# design.net
KiCad netlist of a schematic drawn in EAGLE
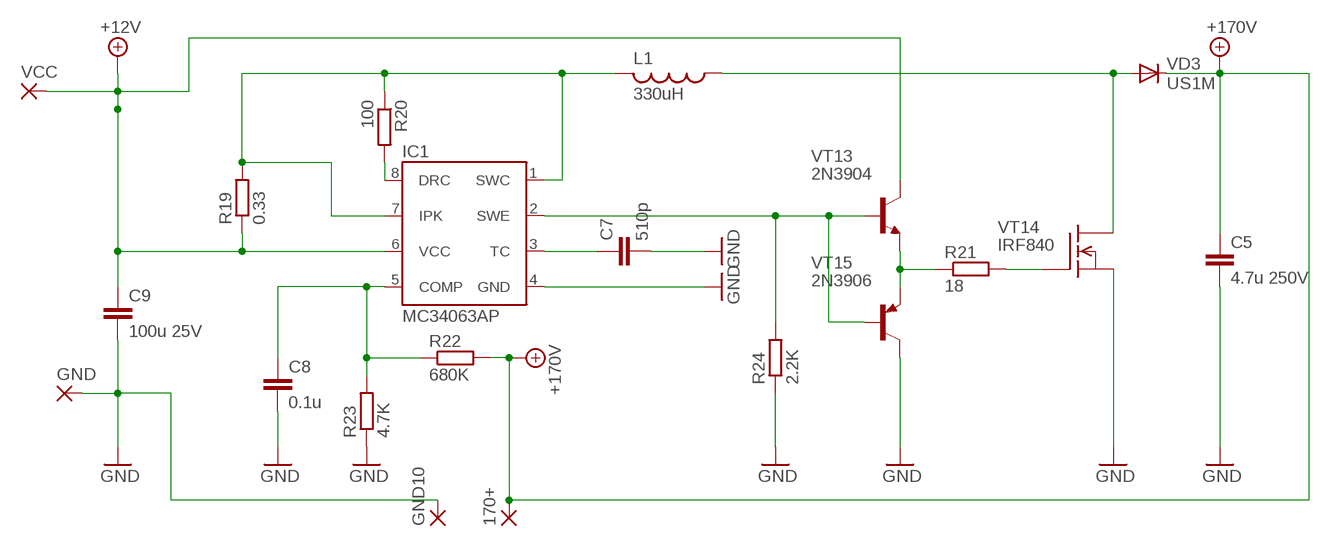
[diagram p0: schematic, sheet 1]

(export (version "E")
  (design (tool "Eeschema 10.0.6"))
  (components
    (comp (ref "170+")
      (value "2,54/0,8")
      (footprint "eagle-import:2,54_0,8")
      (libsource (lib "eagle-import") (part "2,54/0,8"))
    )
    (comp (ref "C5")
      (value "4.7u 250V")
      (footprint "eagle-import:C025-030X050")
      (libsource (lib "eagle-import") (part "C-EU025-030X050"))
    )
    (comp (ref "C7")
      (value "510p")
      (footprint "eagle-import:C025-030X050")
      (libsource (lib "eagle-import") (part "C-EU025-030X050"))
    )
    (comp (ref "C8")
      (value "0.1u")
      (footprint "eagle-import:C025-030X050")
      (libsource (lib "eagle-import") (part "C-EU025-030X050"))
    )
    (comp (ref "C9")
      (value "100u 25V")
      (footprint "eagle-import:C025-030X050")
      (libsource (lib "eagle-import") (part "C-EU025-030X050"))
    )
    (comp (ref "GND")
      (value "2,54/0,8")
      (footprint "eagle-import:2,54_0,8")
      (libsource (lib "eagle-import") (part "2,54/0,8"))
    )
    (comp (ref "GND10")
      (value "2,54/0,8")
      (footprint "eagle-import:2,54_0,8")
      (libsource (lib "eagle-import") (part "2,54/0,8"))
    )
    (comp (ref "IC1")
      (value "MC34063AP")
      (footprint "eagle-import:DIL-08")
      (libsource (lib "eagle-import") (part "MC34063AP"))
    )
    (comp (ref "L1")
      (value "330uH")
      (footprint "eagle-import:0204_5")
      (libsource (lib "eagle-import") (part "L-US0204/5"))
    )
    (comp (ref "R19")
      (value "0.33")
      (footprint "eagle-import:0204_5")
      (libsource (lib "eagle-import") (part "R-EU_0204/5"))
    )
    (comp (ref "R20")
      (value "100")
      (footprint "eagle-import:0204_5")
      (libsource (lib "eagle-import") (part "R-EU_0204/5"))
    )
    (comp (ref "R21")
      (value "18")
      (footprint "eagle-import:0204_5")
      (libsource (lib "eagle-import") (part "R-EU_0204/5"))
    )
    (comp (ref "R22")
      (value "680K")
      (footprint "eagle-import:0204_5")
      (libsource (lib "eagle-import") (part "R-EU_0204/5"))
    )
    (comp (ref "R23")
      (value "4.7K")
      (footprint "eagle-import:0204_5")
      (libsource (lib "eagle-import") (part "R-EU_0204/5"))
    )
    (comp (ref "R24")
      (value "2.2K")
      (footprint "eagle-import:0204_5")
      (libsource (lib "eagle-import") (part "R-EU_0204/5"))
    )
    (comp (ref "VCC")
      (value "2,54/0,8")
      (footprint "eagle-import:2,54_0,8")
      (libsource (lib "eagle-import") (part "2,54/0,8"))
    )
    (comp (ref "VD3")
      (value "US1M")
      (footprint "eagle-import:DO41-10")
      (libsource (lib "eagle-import") (part "1N4004"))
    )
    (comp (ref "VT13")
      (value "2N3904")
      (footprint "eagle-import:TO92")
      (libsource (lib "eagle-import") (part "2N3904"))
    )
    (comp (ref "VT14")
      (value "IRF840")
      (footprint "eagle-import:TO220")
      (libsource (lib "eagle-import") (part "IRF840"))
    )
    (comp (ref "VT15")
      (value "2N3906")
      (footprint "eagle-import:TO92")
      (libsource (lib "eagle-import") (part "2N3906"))
    )
  )
  (nets
    (net (code "1") (name "+12V") (class "Default")
      (node (ref "C9") (pin "1") (pinfunction "1_1") (pintype "passive"))
      (node (ref "IC1") (pin "6") (pinfunction "VCC_6") (pintype "power_in"))
      (node (ref "R19") (pin "1") (pinfunction "1_1") (pintype "passive"))
      (node (ref "VCC") (pin "1") (pinfunction "P_1") (pintype "passive"))
      (node (ref "VT13") (pin "1") (pinfunction "C_1") (pintype "passive"))
    )
    (net (code "2") (name "+170V") (class "Default")
      (node (ref "170+") (pin "1") (pinfunction "P_1") (pintype "passive"))
      (node (ref "C5") (pin "1") (pinfunction "1_1") (pintype "passive"))
      (node (ref "R22") (pin "2") (pinfunction "2_2") (pintype "passive"))
      (node (ref "VD3") (pin "C") (pinfunction "C_C") (pintype "passive"))
    )
    (net (code "3") (name "GND") (class "Default")
      (node (ref "C5") (pin "2") (pinfunction "2_2") (pintype "passive"))
      (node (ref "C7") (pin "2") (pinfunction "2_2") (pintype "passive"))
      (node (ref "C8") (pin "2") (pinfunction "2_2") (pintype "passive"))
      (node (ref "C9") (pin "2") (pinfunction "2_2") (pintype "passive"))
      (node (ref "GND") (pin "1") (pinfunction "P_1") (pintype "passive"))
      (node (ref "GND10") (pin "1") (pinfunction "P_1") (pintype "passive"))
      (node (ref "IC1") (pin "4") (pinfunction "GND_4") (pintype "power_in"))
      (node (ref "R23") (pin "1") (pinfunction "1_1") (pintype "passive"))
      (node (ref "R24") (pin "1") (pinfunction "1_1") (pintype "passive"))
      (node (ref "VT14") (pin "3") (pinfunction "S_3") (pintype "passive"))
      (node (ref "VT15") (pin "1") (pinfunction "C_1") (pintype "passive"))
    )
    (net (code "4") (name "Net-(IC1-COMP)") (class "Default")
      (node (ref "C8") (pin "1") (pinfunction "1_1") (pintype "passive"))
      (node (ref "IC1") (pin "5") (pinfunction "COMP_5") (pintype "input"))
      (node (ref "R22") (pin "1") (pinfunction "1_1") (pintype "passive"))
      (node (ref "R23") (pin "2") (pinfunction "2_2") (pintype "passive"))
    )
    (net (code "5") (name "Net-(IC1-DRC)") (class "Default")
      (node (ref "IC1") (pin "8") (pinfunction "DRC_8") (pintype "input"))
      (node (ref "R20") (pin "2") (pinfunction "2_2") (pintype "passive"))
    )
    (net (code "6") (name "Net-(IC1-IPK)") (class "Default")
      (node (ref "IC1") (pin "1") (pinfunction "SWC_1") (pintype "bidirectional"))
      (node (ref "IC1") (pin "7") (pinfunction "IPK_7") (pintype "input"))
      (node (ref "L1") (pin "2") (pinfunction "2_2") (pintype "passive"))
      (node (ref "R19") (pin "2") (pinfunction "2_2") (pintype "passive"))
      (node (ref "R20") (pin "1") (pinfunction "1_1") (pintype "passive"))
    )
    (net (code "7") (name "Net-(IC1-SWE)") (class "Default")
      (node (ref "IC1") (pin "2") (pinfunction "SWE_2") (pintype "bidirectional"))
      (node (ref "R24") (pin "2") (pinfunction "2_2") (pintype "passive"))
      (node (ref "VT13") (pin "2") (pinfunction "B_2") (pintype "passive"))
      (node (ref "VT15") (pin "2") (pinfunction "B_2") (pintype "passive"))
    )
    (net (code "8") (name "Net-(IC1-TC)") (class "Default")
      (node (ref "C7") (pin "1") (pinfunction "1_1") (pintype "passive"))
      (node (ref "IC1") (pin "3") (pinfunction "TC_3") (pintype "passive"))
    )
    (net (code "9") (name "Net-(VT13-E)") (class "Default")
      (node (ref "R21") (pin "1") (pinfunction "1_1") (pintype "passive"))
      (node (ref "VT13") (pin "3") (pinfunction "E_3") (pintype "passive"))
      (node (ref "VT15") (pin "3") (pinfunction "E_3") (pintype "passive"))
    )
    (net (code "10") (name "Net-(VT14-D)") (class "Default")
      (node (ref "L1") (pin "1") (pinfunction "1_1") (pintype "passive"))
      (node (ref "VD3") (pin "A") (pinfunction "A_A") (pintype "passive"))
      (node (ref "VT14") (pin "2") (pinfunction "D_2") (pintype "passive"))
    )
    (net (code "11") (name "Net-(VT14-G)") (class "Default")
      (node (ref "R21") (pin "2") (pinfunction "2_2") (pintype "passive"))
      (node (ref "VT14") (pin "1") (pinfunction "G_1") (pintype "passive"))
    )
  )
)
